# 03_Dimmer.net
KiCad netlist of a schematic drawn in Altium Designer
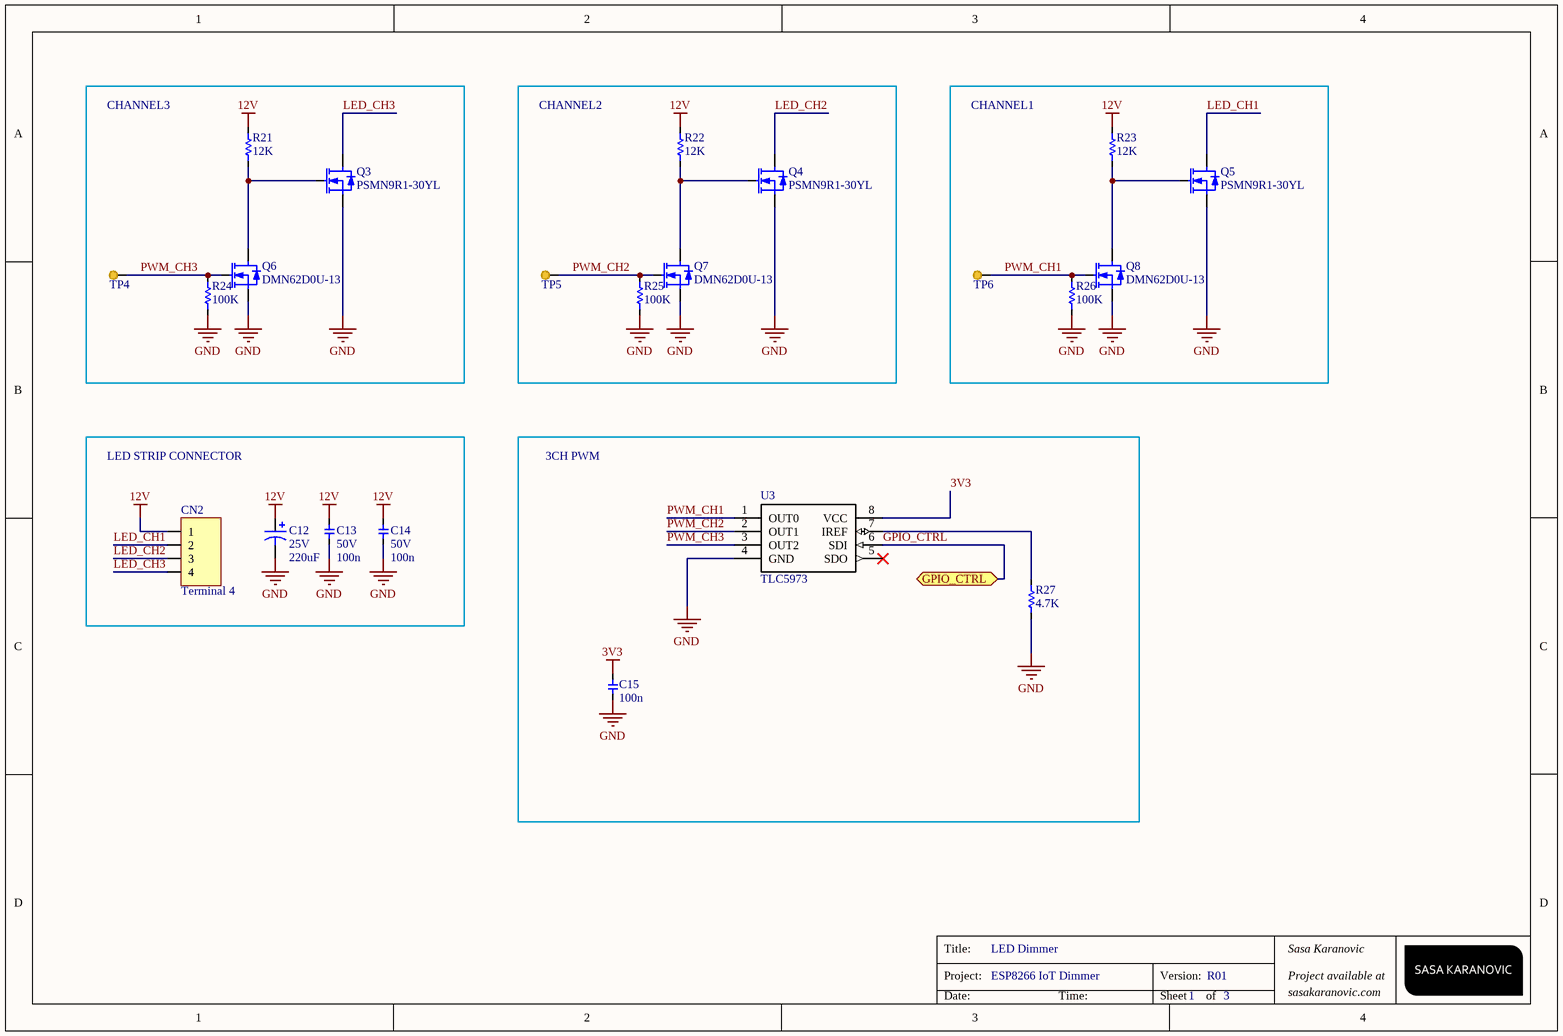
[diagram p0: 03_Dimmer.SchDoc]

(export (version "E")
  (design (tool "Eeschema 10.0.6"))
  (components
    (comp (ref "C12")
      (value "25V")
      (footprint "Moji Footprintovi:Electrolytic Cap 2.54mm")
      (description "Polarized Capacitor (Axial)")
      (fields
        (field (name "MANUFACTURER") "Yageo")
        (field (name "MANUFACTURER PART NUMBER") "AC0603FR-07470RL")
        (field (name "ALTIUM_VALUE") "220uF")
      )
      (libsource (lib "Moji Schematici") (part "Cap Electrolytic"))
    )
    (comp (ref "C13")
      (value "50V")
      (footprint "Moji Footprintovi:0603 - CAP")
      (description "Capacitor")
      (fields
        (field (name "MANUFACTURER") "AVX Corporation")
        (field (name "MANUFACTURER PART NUMBER") "06035C104KAT2A")
        (field (name "ALTIUM_VALUE") "100n")
      )
      (libsource (lib "Moji Schematici") (part "Cap"))
    )
    (comp (ref "C14")
      (value "50V")
      (footprint "Moji Footprintovi:0603 - CAP")
      (description "Capacitor")
      (fields
        (field (name "MANUFACTURER") "AVX Corporation")
        (field (name "MANUFACTURER PART NUMBER") "06035C104KAT2A")
        (field (name "ALTIUM_VALUE") "100n")
      )
      (libsource (lib "Moji Schematici") (part "Cap"))
    )
    (comp (ref "C15")
      (value "100n")
      (footprint "Moji Footprintovi:0603 - CAP")
      (description "Capacitor")
      (fields
        (field (name "MANUFACTURER") "AVX Corporation")
        (field (name "MANUFACTURER PART NUMBER") "06035C104KAT2A")
      )
      (libsource (lib "Moji Schematici") (part "Cap"))
    )
    (comp (ref "CN2")
      (value "Terminal 4")
      (footprint "Moji Footprintovi:Terminal 4_90DEG")
      (description "TERM BLOCK PCB 4POS 5.0MM GREEN")
      (fields
        (field (name "DISTRIBUTOR PART NUMBER") "277-1579-ND")
        (field (name "MANUFACTURER") "Phoenix Contact")
      )
      (libsource (lib "Moji Schematici") (part "Terminal 4"))
    )
    (comp (ref "Q3")
      (value "PSMN9R1-30YL")
      (footprint "Moji Footprintovi:LFPAK-8")
      (description "MOSFET N-CH 30V 37A LFPAK")
      (fields
        (field (name "MANUFACTURER") "Nexperia USA Inc.")
        (field (name "MANUFACTURER PART NUMBER") "PSMN011-30YLC,115")
      )
      (libsource (lib "Moji Schematici") (part "PSMN9R1-30YL"))
    )
    (comp (ref "Q4")
      (value "PSMN9R1-30YL")
      (footprint "Moji Footprintovi:LFPAK-8")
      (description "MOSFET N-CH 30V 37A LFPAK")
      (fields
        (field (name "MANUFACTURER") "Nexperia USA Inc.")
        (field (name "MANUFACTURER PART NUMBER") "PSMN011-30YLC,115")
      )
      (libsource (lib "Moji Schematici") (part "PSMN9R1-30YL"))
    )
    (comp (ref "Q5")
      (value "PSMN9R1-30YL")
      (footprint "Moji Footprintovi:LFPAK-8")
      (description "MOSFET N-CH 30V 37A LFPAK")
      (fields
        (field (name "MANUFACTURER") "Nexperia USA Inc.")
        (field (name "MANUFACTURER PART NUMBER") "PSMN011-30YLC,115")
      )
      (libsource (lib "Moji Schematici") (part "PSMN9R1-30YL"))
    )
    (comp (ref "Q6")
      (value "DMN62D0U-13")
      (footprint "Moji Footprintovi:SOT90P240X100-3N")
      (description "MOSFET N-CH 60V 0.38A")
      (fields
        (field (name "MANUFACTURER") "Diodes Incorporated")
        (field (name "DISTRIBUTOR PART NUMBER") "DMN62D0U-13DICT-ND")
      )
      (libsource (lib "Moji Schematici") (part "DMN62D0U-13"))
    )
    (comp (ref "Q7")
      (value "DMN62D0U-13")
      (footprint "Moji Footprintovi:SOT90P240X100-3N")
      (description "MOSFET N-CH 60V 0.38A")
      (fields
        (field (name "MANUFACTURER") "Diodes Incorporated")
        (field (name "DISTRIBUTOR PART NUMBER") "DMN62D0U-13DICT-ND")
      )
      (libsource (lib "Moji Schematici") (part "DMN62D0U-13"))
    )
    (comp (ref "Q8")
      (value "DMN62D0U-13")
      (footprint "Moji Footprintovi:SOT90P240X100-3N")
      (description "MOSFET N-CH 60V 0.38A")
      (fields
        (field (name "MANUFACTURER") "Diodes Incorporated")
        (field (name "DISTRIBUTOR PART NUMBER") "DMN62D0U-13DICT-ND")
      )
      (libsource (lib "Moji Schematici") (part "DMN62D0U-13"))
    )
    (comp (ref "R21")
      (value "12K")
      (footprint "Moji Footprintovi:0603")
      (description "Resistor")
      (fields
        (field (name "MANUFACTURER") "Yageo")
        (field (name "MANUFACTURER PART NUMBER") "RT0603FRE0712KL")
      )
      (libsource (lib "Moji Schematici") (part "Res"))
    )
    (comp (ref "R22")
      (value "12K")
      (footprint "Moji Footprintovi:0603")
      (description "Resistor")
      (fields
        (field (name "MANUFACTURER") "Yageo")
        (field (name "MANUFACTURER PART NUMBER") "RT0603FRE0712KL")
      )
      (libsource (lib "Moji Schematici") (part "Res"))
    )
    (comp (ref "R23")
      (value "12K")
      (footprint "Moji Footprintovi:0603")
      (description "Resistor")
      (fields
        (field (name "MANUFACTURER") "Yageo")
        (field (name "MANUFACTURER PART NUMBER") "RT0603FRE0712KL")
      )
      (libsource (lib "Moji Schematici") (part "Res"))
    )
    (comp (ref "R24")
      (value "100K")
      (footprint "Moji Footprintovi:0603")
      (description "Resistor")
      (fields
        (field (name "MANUFACTURER") "Yageo")
        (field (name "MANUFACTURER PART NUMBER") "RT0603BRD07100KL")
      )
      (libsource (lib "Moji Schematici") (part "Res"))
    )
    (comp (ref "R25")
      (value "100K")
      (footprint "Moji Footprintovi:0603")
      (description "Resistor")
      (fields
        (field (name "MANUFACTURER") "Yageo")
        (field (name "MANUFACTURER PART NUMBER") "RT0603BRD07100KL")
      )
      (libsource (lib "Moji Schematici") (part "Res"))
    )
    (comp (ref "R26")
      (value "100K")
      (footprint "Moji Footprintovi:0603")
      (description "Resistor")
      (fields
        (field (name "MANUFACTURER") "Yageo")
        (field (name "MANUFACTURER PART NUMBER") "RT0603BRD07100KL")
      )
      (libsource (lib "Moji Schematici") (part "Res"))
    )
    (comp (ref "R27")
      (value "4.7K")
      (footprint "Moji Footprintovi:0603")
      (description "Resistor")
      (fields
        (field (name "MANUFACTURER") "Yageo")
        (field (name "MANUFACTURER PART NUMBER") "RT0603FRE074K7L")
      )
      (libsource (lib "Moji Schematici") (part "Res"))
    )
    (comp (ref "TP4")
      (value "Test Point 0.6mm")
      (footprint "Moji Footprintovi:TP_SMD_1mm")
      (libsource (lib "Moji Schematici") (part "TP"))
    )
    (comp (ref "TP5")
      (value "Test Point 0.6mm")
      (footprint "Moji Footprintovi:TP_SMD_1mm")
      (libsource (lib "Moji Schematici") (part "TP"))
    )
    (comp (ref "TP6")
      (value "Test Point 0.6mm")
      (footprint "Moji Footprintovi:TP_SMD_1mm")
      (libsource (lib "Moji Schematici") (part "TP"))
    )
    (comp (ref "U3")
      (value "TLC5973")
      (footprint "*SOIC127P600X175-8N")
      (description "TLC5973 3-Channel, 12-Bit, PWM Constant-Current LED Driver  with Single-Wire Interface")
      (fields (field (name "MANUFACTURER PART NUMBER") "TLC5973DR"))
      (libsource (lib "MyIntegratedLibrary") (part "TLC5973"))
    )
  )
  (nets
    (net (code "1") (name "/GPIO_CTRL") (class "Default")
      (node (ref "U3") (pin "6") (pinfunction "SDI_6") (pintype "input"))
    )
    (net (code "2") (name "/LED_CH1") (class "Default")
      (node (ref "CN2") (pin "2") (pinfunction "2_2") (pintype "passive"))
      (node (ref "Q5") (pin "D") (pinfunction "D_D") (pintype "passive"))
    )
    (net (code "3") (name "/LED_CH2") (class "Default")
      (node (ref "CN2") (pin "3") (pinfunction "3_3") (pintype "passive"))
      (node (ref "Q4") (pin "D") (pinfunction "D_D") (pintype "passive"))
    )
    (net (code "4") (name "/LED_CH3") (class "Default")
      (node (ref "CN2") (pin "4") (pinfunction "4_4") (pintype "passive"))
      (node (ref "Q3") (pin "D") (pinfunction "D_D") (pintype "passive"))
    )
    (net (code "5") (name "/PWM_CH1") (class "Default")
      (node (ref "Q8") (pin "1") (pinfunction "G_1") (pintype "passive"))
      (node (ref "R26") (pin "2") (pinfunction "2_2") (pintype "passive"))
      (node (ref "TP6") (pin "1") (pinfunction "1_1") (pintype "passive"))
      (node (ref "U3") (pin "1") (pinfunction "OUT0_1") (pintype "passive"))
    )
    (net (code "6") (name "/PWM_CH2") (class "Default")
      (node (ref "Q7") (pin "1") (pinfunction "G_1") (pintype "passive"))
      (node (ref "R25") (pin "2") (pinfunction "2_2") (pintype "passive"))
      (node (ref "TP5") (pin "1") (pinfunction "1_1") (pintype "passive"))
      (node (ref "U3") (pin "2") (pinfunction "OUT1_2") (pintype "passive"))
    )
    (net (code "7") (name "/PWM_CH3") (class "Default")
      (node (ref "Q6") (pin "1") (pinfunction "G_1") (pintype "passive"))
      (node (ref "R24") (pin "2") (pinfunction "2_2") (pintype "passive"))
      (node (ref "TP4") (pin "1") (pinfunction "1_1") (pintype "passive"))
      (node (ref "U3") (pin "3") (pinfunction "OUT2_3") (pintype "passive"))
    )
    (net (code "8") (name "3V3") (class "Default")
      (node (ref "C15") (pin "2") (pinfunction "2_2") (pintype "passive"))
      (node (ref "U3") (pin "8") (pinfunction "VCC_8") (pintype "power_in"))
    )
    (net (code "9") (name "12V") (class "Default")
      (node (ref "C12") (pin "1") (pinfunction "1_1") (pintype "passive"))
      (node (ref "C13") (pin "2") (pinfunction "2_2") (pintype "passive"))
      (node (ref "C14") (pin "2") (pinfunction "2_2") (pintype "passive"))
      (node (ref "CN2") (pin "1") (pinfunction "1_1") (pintype "passive"))
      (node (ref "R21") (pin "2") (pinfunction "2_2") (pintype "passive"))
      (node (ref "R22") (pin "2") (pinfunction "2_2") (pintype "passive"))
      (node (ref "R23") (pin "2") (pinfunction "2_2") (pintype "passive"))
    )
    (net (code "10") (name "GND") (class "Default")
      (node (ref "C12") (pin "2") (pinfunction "2_2") (pintype "passive"))
      (node (ref "C13") (pin "1") (pinfunction "1_1") (pintype "passive"))
      (node (ref "C14") (pin "1") (pinfunction "1_1") (pintype "passive"))
      (node (ref "C15") (pin "1") (pinfunction "1_1") (pintype "passive"))
      (node (ref "Q3") (pin "S") (pinfunction "S_S") (pintype "passive"))
      (node (ref "Q4") (pin "S") (pinfunction "S_S") (pintype "passive"))
      (node (ref "Q5") (pin "S") (pinfunction "S_S") (pintype "passive"))
      (node (ref "Q6") (pin "3") (pinfunction "S_3") (pintype "passive"))
      (node (ref "Q7") (pin "3") (pinfunction "S_3") (pintype "passive"))
      (node (ref "Q8") (pin "3") (pinfunction "S_3") (pintype "passive"))
      (node (ref "R24") (pin "1") (pinfunction "1_1") (pintype "passive"))
      (node (ref "R25") (pin "1") (pinfunction "1_1") (pintype "passive"))
      (node (ref "R26") (pin "1") (pinfunction "1_1") (pintype "passive"))
      (node (ref "R27") (pin "1") (pinfunction "1_1") (pintype "passive"))
      (node (ref "U3") (pin "4") (pinfunction "GND_4") (pintype "passive"))
    )
    (net (code "11") (name "Net-(Q6-D)") (class "Default")
      (node (ref "Q3") (pin "G") (pinfunction "G_G") (pintype "passive"))
      (node (ref "Q6") (pin "2") (pinfunction "D_2") (pintype "passive"))
      (node (ref "R21") (pin "1") (pinfunction "1_1") (pintype "passive"))
    )
    (net (code "12") (name "Net-(Q7-D)") (class "Default")
      (node (ref "Q4") (pin "G") (pinfunction "G_G") (pintype "passive"))
      (node (ref "Q7") (pin "2") (pinfunction "D_2") (pintype "passive"))
      (node (ref "R22") (pin "1") (pinfunction "1_1") (pintype "passive"))
    )
    (net (code "13") (name "Net-(Q8-D)") (class "Default")
      (node (ref "Q5") (pin "G") (pinfunction "G_G") (pintype "passive"))
      (node (ref "Q8") (pin "2") (pinfunction "D_2") (pintype "passive"))
      (node (ref "R23") (pin "1") (pinfunction "1_1") (pintype "passive"))
    )
    (net (code "14") (name "Net-(U3-IREF)") (class "Default")
      (node (ref "R27") (pin "2") (pinfunction "2_2") (pintype "passive"))
      (node (ref "U3") (pin "7") (pinfunction "IREF_7") (pintype "bidirectional"))
    )
    (net (code "15") (name "unconnected-(U3-SDO-Pad5)") (class "Default")
      (node (ref "U3") (pin "5") (pinfunction "SDO_5") (pintype "output+no_connect"))
    )
  )
)
